# Input_Power.net
KiCad netlist of a schematic drawn in Altium Designer
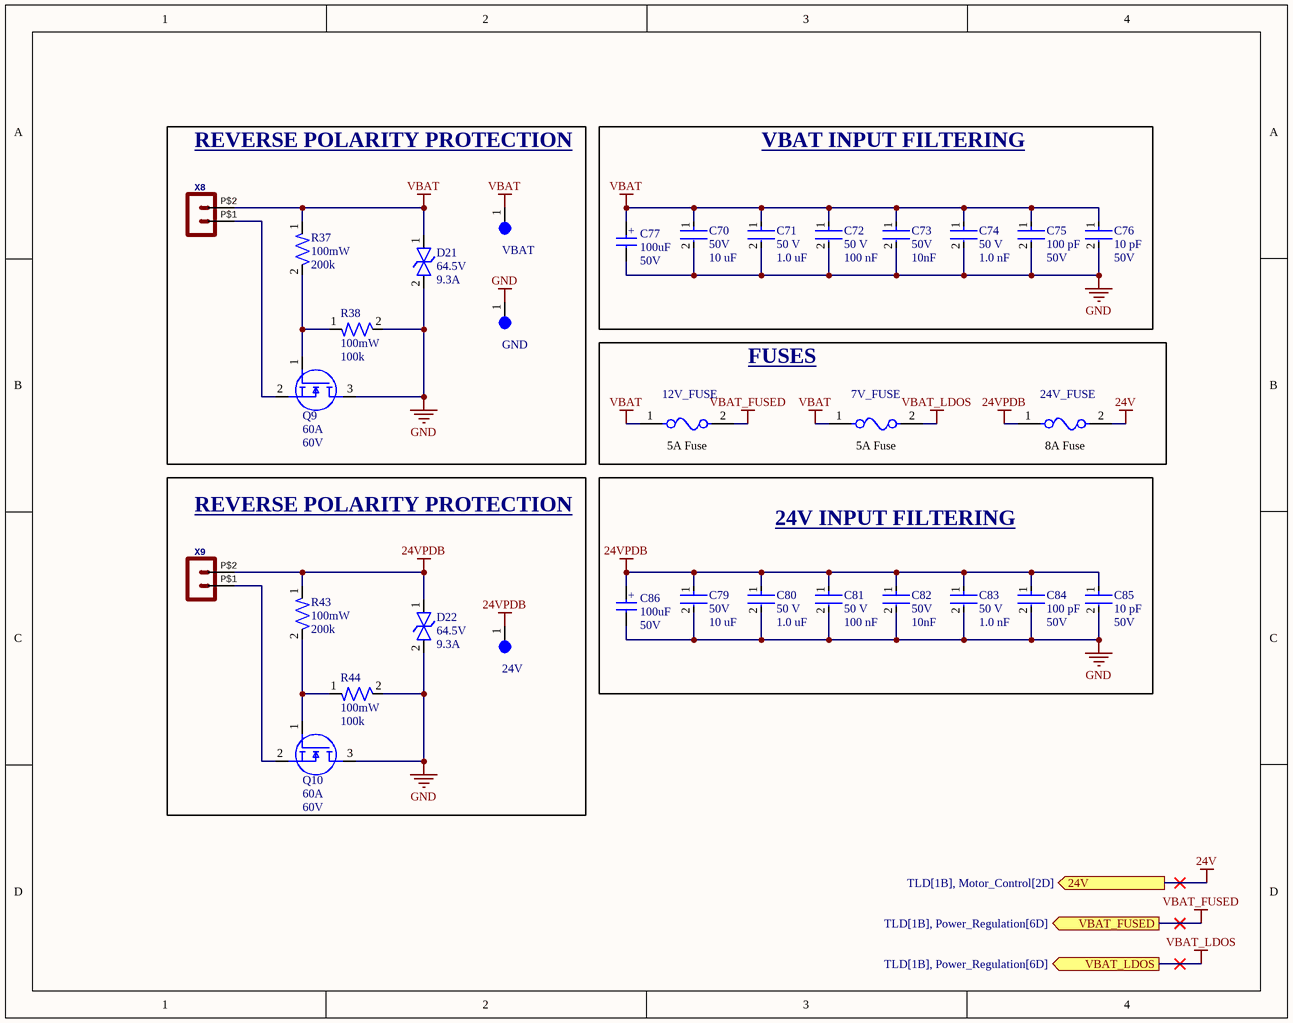
[diagram p0: Input_Power.SchDoc]

(export (version "E")
  (design (tool "Eeschema 10.0.6"))
  (components
    (comp (ref "7V_FUSE")
      (value "01550900M")
      (footprint "FUSE-0001")
      (description "FUSE BLOK CARTRIDGE 125V 10A SMD")
      (libsource (lib "JLC_25") (part "FUSE-0001"))
    )
    (comp (ref "12V_FUSE")
      (value "01550900M")
      (footprint "FUSE-0001")
      (description "FUSE BLOK CARTRIDGE 125V 10A SMD")
      (libsource (lib "JLC_25") (part "FUSE-0001"))
    )
    (comp (ref "24V")
      (value "5003")
      (footprint "TEST-POINT-0001")
      (description "Oranange PC Test Point, Miniature Phoisphor Bronze Silver Plating Through Hole Mounting Type")
      (libsource (lib "*") (part "TEST-POINT-0001"))
    )
    (comp (ref "24V_FUSE")
      (value "01550900M")
      (footprint "FUSE-0001")
      (description "FUSE BLOK CARTRIDGE 125V 10A SMD")
      (libsource (lib "JLC_25") (part "FUSE-0001"))
    )
    (comp (ref "C70")
      (value "CL32B106KBJNNNE")
      (footprint "CAP-1210")
      (description "CAP CER 10UF 50V X7R 1210")
      (fields (field (name "VOLTAGE") "50V") (field (name "CAPACITANCE") "10 uF"))
      (libsource (lib "JLC_25") (part "CAP-10U-0002"))
    )
    (comp (ref "C71")
      (value "CC0805KKX7R9BB105")
      (footprint "CAP-0805")
      (description "CAP CER 1UF 50V X7R 0805")
      (fields (field (name "VOLTAGE") "50 V") (field (name "CAPACITANCE") "1.0 uF"))
      (libsource (lib "JLC_25") (part "CAP-1U-0001"))
    )
    (comp (ref "C72")
      (value "CC0805KRX7R9BB104")
      (footprint "CAP-0805")
      (description "CAP CER 0.1UF 50V X7R 0805")
      (fields (field (name "VOLTAGE RATING") "50 V") (field (name "CAPACITANCE") "100 nF"))
      (libsource (lib "JLC_25") (part "CAP-0.1U-0002"))
    )
    (comp (ref "C73")
      (value "GRM2195C1H103JA01D")
      (footprint "CAP-0805")
      (description "CAP CER 10000PF 50V C0G/NP0 0805")
      (fields (field (name "VOLTAGE") "50V") (field (name "CAPACITANCE") "10nF"))
      (libsource (lib "JLC_25") (part "CAP-10N-0001"))
    )
    (comp (ref "C74")
      (value "CC0402KRX7R9BB102")
      (footprint "CAP-0402")
      (description "CAP CER 1000PF 50V X7R 0402")
      (fields (field (name "VOLTAGE") "50 V") (field (name "CAPACITANCE") "1.0 nF"))
      (libsource (lib "JLC_25") (part "CAP-1N-0001"))
    )
    (comp (ref "C75")
      (value "CC0402JRNPO9BN101")
      (footprint "CAP-0402")
      (description "CAP CER 100PF 50V C0G/NPO 0402")
      (fields (field (name "CAPACITANCE") "100 pF") (field (name "VOLTAGE") "50V"))
      (libsource (lib "JLC_25") (part "CAP-100P-0001"))
    )
    (comp (ref "C76")
      (value "CC0402JRNPO9BN100")
      (footprint "CAP-0402")
      (description "CAP CER 10PF 50V C0G/NPO 0402")
      (fields (field (name "CAPACITANCE") "10 pF") (field (name "VOLTAGE") "50V"))
      (libsource (lib "JLC_25") (part "CAP-10P-0001"))
    )
    (comp (ref "C77")
      (value "860040674004")
      (footprint "WCAP-ATUL_8X11.5(DXL)")
      (description "100 µF 50 V Aluminum Electrolytic Capacitors Radial, Can 7000 Hrs @ 105°C")
      (fields
        (field (name "MF") "{'manufacturer': u'~{W}xfcrth Elektronik'}")
        (field (name "CAPACITANCE") "100uF")
        (field (name "VOLTAGE") "50V")
      )
      (libsource (lib "MasterLib") (part "CAP-100u-0001"))
    )
    (comp (ref "C79")
      (value "CL32B106KBJNNNE")
      (footprint "CAP-1210")
      (description "CAP CER 10UF 50V X7R 1210")
      (fields (field (name "VOLTAGE") "50V") (field (name "CAPACITANCE") "10 uF"))
      (libsource (lib "JLC_25") (part "CAP-10U-0002"))
    )
    (comp (ref "C80")
      (value "CC0805KKX7R9BB105")
      (footprint "CAP-0805")
      (description "CAP CER 1UF 50V X7R 0805")
      (fields (field (name "VOLTAGE") "50 V") (field (name "CAPACITANCE") "1.0 uF"))
      (libsource (lib "JLC_25") (part "CAP-1U-0001"))
    )
    (comp (ref "C81")
      (value "CC0805KRX7R9BB104")
      (footprint "CAP-0805")
      (description "CAP CER 0.1UF 50V X7R 0805")
      (fields (field (name "VOLTAGE RATING") "50 V") (field (name "CAPACITANCE") "100 nF"))
      (libsource (lib "JLC_25") (part "CAP-0.1U-0002"))
    )
    (comp (ref "C82")
      (value "GRM2195C1H103JA01D")
      (footprint "CAP-0805")
      (description "CAP CER 10000PF 50V C0G/NP0 0805")
      (fields (field (name "VOLTAGE") "50V") (field (name "CAPACITANCE") "10nF"))
      (libsource (lib "JLC_25") (part "CAP-10N-0001"))
    )
    (comp (ref "C83")
      (value "CC0402KRX7R9BB102")
      (footprint "CAP-0402")
      (description "CAP CER 1000PF 50V X7R 0402")
      (fields (field (name "VOLTAGE") "50 V") (field (name "CAPACITANCE") "1.0 nF"))
      (libsource (lib "JLC_25") (part "CAP-1N-0001"))
    )
    (comp (ref "C84")
      (value "CC0402JRNPO9BN101")
      (footprint "CAP-0402")
      (description "CAP CER 100PF 50V C0G/NPO 0402")
      (fields (field (name "CAPACITANCE") "100 pF") (field (name "VOLTAGE") "50V"))
      (libsource (lib "JLC_25") (part "CAP-100P-0001"))
    )
    (comp (ref "C85")
      (value "CC0402JRNPO9BN100")
      (footprint "CAP-0402")
      (description "CAP CER 10PF 50V C0G/NPO 0402")
      (fields (field (name "CAPACITANCE") "10 pF") (field (name "VOLTAGE") "50V"))
      (libsource (lib "JLC_25") (part "CAP-10P-0001"))
    )
    (comp (ref "C86")
      (value "860040674004")
      (footprint "WCAP-ATUL_8X11.5(DXL)")
      (description "100 µF 50 V Aluminum Electrolytic Capacitors Radial, Can 7000 Hrs @ 105°C")
      (fields
        (field (name "MF") "{'manufacturer': u'~{W}xfcrth Elektronik'}")
        (field (name "CAPACITANCE") "100uF")
        (field (name "VOLTAGE") "50V")
      )
      (libsource (lib "MasterLib") (part "CAP-100u-0001"))
    )
    (comp (ref "D21")
      (value "SMBJ40CA")
      (footprint "DO-214AA (SMBJ)")
      (description "TVS DIODE 40VWM 64.5VC DO214AA")
      (fields (field (name "VOLTAGE RATING") "64.5V") (field (name "CURRENT RATING") "9.3A"))
      (libsource (lib "JLC_25") (part "DIO-TVS-0001"))
    )
    (comp (ref "D22")
      (value "SMBJ40CA")
      (footprint "DO-214AA (SMBJ)")
      (description "TVS DIODE 40VWM 64.5VC DO214AA")
      (fields (field (name "VOLTAGE RATING") "64.5V") (field (name "CURRENT RATING") "9.3A"))
      (libsource (lib "JLC_25") (part "DIO-TVS-0001"))
    )
    (comp (ref "GND")
      (value "5003")
      (footprint "TEST-POINT-0001")
      (description "Oranange PC Test Point, Miniature Phoisphor Bronze Silver Plating Through Hole Mounting Type")
      (libsource (lib "*") (part "TEST-POINT-0001"))
    )
    (comp (ref "Q9")
      (value "CSD18543Q3AT")
      (footprint "IC-8VSONCLIP")
      (description "MOSFET N-CH 60V 12A/60A 8VSON")
      (fields (field (name "VOLTAGE") "60V") (field (name "CONTINUOUS CURRENT") "60A"))
      (libsource (lib "JLC_25") (part "NMOS-60A-0001"))
    )
    (comp (ref "Q10")
      (value "CSD18543Q3AT")
      (footprint "IC-8VSONCLIP")
      (description "MOSFET N-CH 60V 12A/60A 8VSON")
      (fields (field (name "VOLTAGE") "60V") (field (name "CONTINUOUS CURRENT") "60A"))
      (libsource (lib "JLC_25") (part "NMOS-60A-0001"))
    )
    (comp (ref "R37")
      (value "RC0603FR-07200KL")
      (footprint "RES-0603")
      (description "RES SMD 200K OHM 1% 1/10W 0603")
      (fields
        (field (name "TOLERANCE") "1%")
        (field (name "POWER") "100mW")
        (field (name "RESISTANCE") "200k")
      )
      (libsource (lib "JLC_25") (part "RES-200k-0001"))
    )
    (comp (ref "R38")
      (value "RC0603FR-07100KL")
      (footprint "RES-0603")
      (description "RES SMD 100K OHM 1% 1/10W 0603")
      (fields
        (field (name "TOLERANCE") "1%")
        (field (name "POWER") "100mW")
        (field (name "RESISTANCE") "100k")
      )
      (libsource (lib "JLC_25") (part "RES-100k-0001"))
    )
    (comp (ref "R43")
      (value "RC0603FR-07200KL")
      (footprint "RES-0603")
      (description "RES SMD 200K OHM 1% 1/10W 0603")
      (fields
        (field (name "TOLERANCE") "1%")
        (field (name "POWER") "100mW")
        (field (name "RESISTANCE") "200k")
      )
      (libsource (lib "JLC_25") (part "RES-200k-0001"))
    )
    (comp (ref "R44")
      (value "RC0603FR-07100KL")
      (footprint "RES-0603")
      (description "RES SMD 100K OHM 1% 1/10W 0603")
      (fields
        (field (name "TOLERANCE") "1%")
        (field (name "POWER") "100mW")
        (field (name "RESISTANCE") "100k")
      )
      (libsource (lib "JLC_25") (part "RES-100k-0001"))
    )
    (comp (ref "VBAT")
      (value "5003")
      (footprint "TEST-POINT-0001")
      (description "Oranange PC Test Point, Miniature Phoisphor Bronze Silver Plating Through Hole Mounting Type")
      (libsource (lib "*") (part "TEST-POINT-0001"))
    )
    (comp (ref "X8")
      (value "Molex - Micro-Fit 3.0 Series connector,  3.00mm (0.118\") pitch header, 2 positions.")
      (footprint "43045-0200")
      (libsource (lib "MasterLib") (part "HEADER_POS2_43045-0200"))
    )
    (comp (ref "X9")
      (value "Molex - Micro-Fit 3.0 Series connector,  3.00mm (0.118\") pitch header, 2 positions.")
      (footprint "43045-0200")
      (libsource (lib "MasterLib") (part "HEADER_POS2_43045-0200"))
    )
  )
  (nets
    (net (code "1") (name "24V") (class "Default")
      (node (ref "24V_FUSE") (pin "2") (pinfunction "2_2") (pintype "passive"))
    )
    (net (code "2") (name "24VPDB") (class "Default")
      (node (ref "24V") (pin "1") (pinfunction "0_1") (pintype "passive"))
      (node (ref "24V_FUSE") (pin "1") (pinfunction "1_1") (pintype "passive"))
      (node (ref "C79") (pin "1") (pinfunction "1_1") (pintype "passive"))
      (node (ref "C80") (pin "1") (pinfunction "1_1") (pintype "passive"))
      (node (ref "C81") (pin "1") (pinfunction "1_1") (pintype "passive"))
      (node (ref "C82") (pin "1") (pinfunction "1_1") (pintype "passive"))
      (node (ref "C83") (pin "1") (pinfunction "1_1") (pintype "passive"))
      (node (ref "C84") (pin "1") (pinfunction "1_1") (pintype "passive"))
      (node (ref "C85") (pin "1") (pinfunction "1_1") (pintype "passive"))
      (node (ref "C86") (pin "1") (pinfunction "POS_1") (pintype "passive"))
      (node (ref "D22") (pin "1") (pintype "passive"))
      (node (ref "R43") (pin "1") (pinfunction "1_1") (pintype "passive"))
      (node (ref "X9") (pin "P$2") (pinfunction "2_P$2") (pintype "passive"))
    )
    (net (code "3") (name "GND") (class "Default")
      (node (ref "C70") (pin "2") (pinfunction "2_2") (pintype "passive"))
      (node (ref "C71") (pin "2") (pinfunction "2_2") (pintype "passive"))
      (node (ref "C72") (pin "2") (pinfunction "2_2") (pintype "passive"))
      (node (ref "C73") (pin "2") (pinfunction "2_2") (pintype "passive"))
      (node (ref "C74") (pin "2") (pinfunction "2_2") (pintype "passive"))
      (node (ref "C75") (pin "2") (pinfunction "2_2") (pintype "passive"))
      (node (ref "C76") (pin "2") (pinfunction "2_2") (pintype "passive"))
      (node (ref "C77") (pin "2") (pinfunction "NEG_2") (pintype "passive"))
      (node (ref "C79") (pin "2") (pinfunction "2_2") (pintype "passive"))
      (node (ref "C80") (pin "2") (pinfunction "2_2") (pintype "passive"))
      (node (ref "C81") (pin "2") (pinfunction "2_2") (pintype "passive"))
      (node (ref "C82") (pin "2") (pinfunction "2_2") (pintype "passive"))
      (node (ref "C83") (pin "2") (pinfunction "2_2") (pintype "passive"))
      (node (ref "C84") (pin "2") (pinfunction "2_2") (pintype "passive"))
      (node (ref "C85") (pin "2") (pinfunction "2_2") (pintype "passive"))
      (node (ref "C86") (pin "2") (pinfunction "NEG_2") (pintype "passive"))
      (node (ref "D21") (pin "2") (pintype "passive"))
      (node (ref "D22") (pin "2") (pintype "passive"))
      (node (ref "GND") (pin "1") (pinfunction "0_1") (pintype "passive"))
      (node (ref "Q10") (pin "3") (pinfunction "D_3") (pintype "passive"))
      (node (ref "Q9") (pin "3") (pinfunction "D_3") (pintype "passive"))
      (node (ref "R38") (pin "2") (pinfunction "2_2") (pintype "passive"))
      (node (ref "R44") (pin "2") (pinfunction "2_2") (pintype "passive"))
    )
    (net (code "4") (name "Net-(Q9-G)") (class "Default")
      (node (ref "Q9") (pin "1") (pinfunction "G_1") (pintype "passive"))
      (node (ref "R37") (pin "2") (pinfunction "2_2") (pintype "passive"))
      (node (ref "R38") (pin "1") (pinfunction "1_1") (pintype "passive"))
    )
    (net (code "5") (name "Net-(Q9-S)") (class "Default")
      (node (ref "Q9") (pin "2") (pinfunction "S_2") (pintype "passive"))
      (node (ref "X8") (pin "P$1") (pinfunction "1_P$1") (pintype "passive"))
    )
    (net (code "6") (name "Net-(Q10-G)") (class "Default")
      (node (ref "Q10") (pin "1") (pinfunction "G_1") (pintype "passive"))
      (node (ref "R43") (pin "2") (pinfunction "2_2") (pintype "passive"))
      (node (ref "R44") (pin "1") (pinfunction "1_1") (pintype "passive"))
    )
    (net (code "7") (name "Net-(Q10-S)") (class "Default")
      (node (ref "Q10") (pin "2") (pinfunction "S_2") (pintype "passive"))
      (node (ref "X9") (pin "P$1") (pinfunction "1_P$1") (pintype "passive"))
    )
    (net (code "8") (name "VBAT") (class "Default")
      (node (ref "12V_FUSE") (pin "1") (pinfunction "1_1") (pintype "passive"))
      (node (ref "7V_FUSE") (pin "1") (pinfunction "1_1") (pintype "passive"))
      (node (ref "C70") (pin "1") (pinfunction "1_1") (pintype "passive"))
      (node (ref "C71") (pin "1") (pinfunction "1_1") (pintype "passive"))
      (node (ref "C72") (pin "1") (pinfunction "1_1") (pintype "passive"))
      (node (ref "C73") (pin "1") (pinfunction "1_1") (pintype "passive"))
      (node (ref "C74") (pin "1") (pinfunction "1_1") (pintype "passive"))
      (node (ref "C75") (pin "1") (pinfunction "1_1") (pintype "passive"))
      (node (ref "C76") (pin "1") (pinfunction "1_1") (pintype "passive"))
      (node (ref "C77") (pin "1") (pinfunction "POS_1") (pintype "passive"))
      (node (ref "D21") (pin "1") (pintype "passive"))
      (node (ref "R37") (pin "1") (pinfunction "1_1") (pintype "passive"))
      (node (ref "VBAT") (pin "1") (pinfunction "0_1") (pintype "passive"))
      (node (ref "X8") (pin "P$2") (pinfunction "2_P$2") (pintype "passive"))
    )
    (net (code "9") (name "VBAT_FUSED") (class "Default")
      (node (ref "12V_FUSE") (pin "2") (pinfunction "2_2") (pintype "passive"))
    )
    (net (code "10") (name "VBAT_LDOS") (class "Default")
      (node (ref "7V_FUSE") (pin "2") (pinfunction "2_2") (pintype "passive"))
    )
  )
)
